# Sheet1.net
KiCad netlist of a schematic drawn in Altium Designer
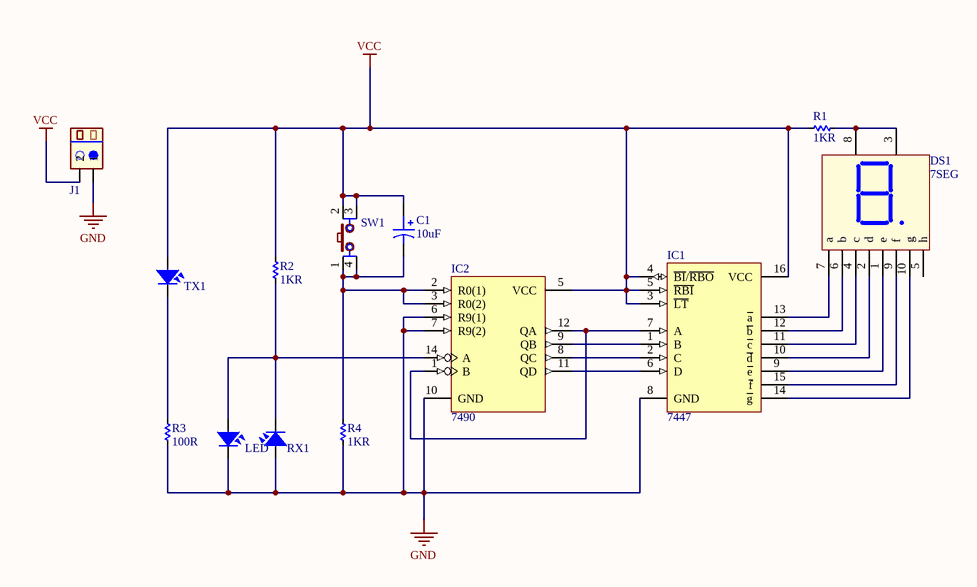
[diagram p0: Sheet1.SchDoc]

(export (version "E")
  (design (tool "Eeschema 10.0.6"))
  (components
    (comp (ref "C1")
      (value "10uF")
      (footprint "RADIAL C")
      (description "Polarized Capacitor")
      (fields (field (name "Comment") "Cap Pol") (field (name "PUBLISHER") "Altium Limited"))
      (libsource (lib "hphonglib") (part "Cap Pol"))
    )
    (comp (ref "DS1")
      (value "7SEG")
      (footprint "LED7SEG-1-0.56")
      (description "14.2 mm General Purpose Blue 7-Segment Display: CC, RH DP, Gray Surface")
      (fields (field (name "PUBLISHER") "Altium Limited"))
      (libsource (lib "LIBRARY") (part "LED7SEG-1"))
    )
    (comp (ref "IC1")
      (value "7447")
      (footprint "DIP16")
      (description "BCD to 7-Segment Decoder/Driver")
      (libsource (lib "LIBRARY") (part "7447"))
    )
    (comp (ref "IC2")
      (value "7490")
      (footprint "DIP14")
      (description "4-Bit Decade Counter")
      (libsource (lib "LIBRARY") (part "7490"))
    )
    (comp (ref "J1")
      (value "CON.Domino2")
      (footprint "Domino 2M")
      (description "2 pins Domino Header")
      (fields (field (name "PUBLISHER") "Hoang Nguyen"))
      (libsource (lib "hphonglib") (part "CON.Domino2"))
    )
    (comp (ref "LED")
      (value "LED")
      (footprint "LED-5-RED")
      (description "LED Single colour Green and Red")
      (libsource (lib "LIBRARY") (part "LED"))
    )
    (comp (ref "R1")
      (value "1KR")
      (footprint "RES-1/4W")
      (description "Res")
      (fields
        (field (name "MANUFACTURER") "Generic Components")
        (field (name "PUBLISHER") "Altium Hobart Technology Centre")
      )
      (libsource (lib "LIBRARY") (part "Res"))
    )
    (comp (ref "R2")
      (value "1KR")
      (footprint "RES-1/4W")
      (description "Res")
      (fields
        (field (name "MANUFACTURER") "Generic Components")
        (field (name "PUBLISHER") "Altium Hobart Technology Centre")
      )
      (libsource (lib "LIBRARY") (part "Res"))
    )
    (comp (ref "R3")
      (value "100R")
      (footprint "RES-1/4W")
      (description "Res")
      (fields
        (field (name "MANUFACTURER") "Generic Components")
        (field (name "PUBLISHER") "Altium Hobart Technology Centre")
      )
      (libsource (lib "LIBRARY") (part "Res"))
    )
    (comp (ref "R4")
      (value "1KR")
      (footprint "RES-1/4W")
      (description "Res")
      (fields
        (field (name "MANUFACTURER") "Generic Components")
        (field (name "PUBLISHER") "Altium Hobart Technology Centre")
      )
      (libsource (lib "LIBRARY") (part "Res"))
    )
    (comp (ref "RX1")
      (value "LED")
      (footprint "LED-5MM-BLUE")
      (description "LED Single colour Green and Red")
      (libsource (lib "LIBRARY") (part "LED"))
    )
    (comp (ref "SW1")
      (value "SW")
      (footprint "SW2-DIP")
      (description "Switch button 4 pin")
      (libsource (lib "LIBRARY") (part "SW4"))
    )
    (comp (ref "TX1")
      (value "LED")
      (footprint "LED-5MM-WHITE")
      (description "LED Single colour Green and Red")
      (libsource (lib "LIBRARY") (part "LED"))
    )
  )
  (nets
    (net (code "1") (name "GND") (class "Default")
      (node (ref "IC1") (pin "8") (pinfunction "GND_8") (pintype "power_in"))
      (node (ref "IC2") (pin "10") (pinfunction "GND_10") (pintype "power_in"))
      (node (ref "IC2") (pin "6") (pinfunction "R9(1)_6") (pintype "input"))
      (node (ref "IC2") (pin "7") (pinfunction "R9(2)_7") (pintype "input"))
      (node (ref "J1") (pin "1") (pinfunction "1_1") (pintype "passive"))
      (node (ref "LED") (pin "2") (pinfunction "2_2") (pintype "passive"))
      (node (ref "R3") (pin "2") (pinfunction "2_2") (pintype "passive"))
      (node (ref "R4") (pin "2") (pinfunction "2_2") (pintype "passive"))
      (node (ref "RX1") (pin "1") (pinfunction "1_1") (pintype "passive"))
    )
    (net (code "2") (name "Net-(DS1-Vcc-Pad3)") (class "Default")
      (node (ref "DS1") (pin "3") (pinfunction "Vcc_3") (pintype "passive"))
      (node (ref "DS1") (pin "8") (pinfunction "Vcc_8") (pintype "passive"))
      (node (ref "R1") (pin "2") (pinfunction "2_2") (pintype "passive"))
    )
    (net (code "3") (name "Net-(DS1-a)") (class "Default")
      (node (ref "DS1") (pin "7") (pinfunction "a_7") (pintype "passive"))
      (node (ref "IC1") (pin "13") (pinfunction "~{a}_13") (pintype "open_collector"))
    )
    (net (code "4") (name "Net-(DS1-b)") (class "Default")
      (node (ref "DS1") (pin "6") (pinfunction "b_6") (pintype "passive"))
      (node (ref "IC1") (pin "12") (pinfunction "~{b}_12") (pintype "open_collector"))
    )
    (net (code "5") (name "Net-(DS1-c)") (class "Default")
      (node (ref "DS1") (pin "4") (pinfunction "c_4") (pintype "passive"))
      (node (ref "IC1") (pin "11") (pinfunction "~{c}_11") (pintype "open_collector"))
    )
    (net (code "6") (name "Net-(DS1-d)") (class "Default")
      (node (ref "DS1") (pin "2") (pinfunction "d_2") (pintype "passive"))
      (node (ref "IC1") (pin "10") (pinfunction "~{d}_10") (pintype "open_collector"))
    )
    (net (code "7") (name "Net-(DS1-e)") (class "Default")
      (node (ref "DS1") (pin "1") (pinfunction "e_1") (pintype "passive"))
      (node (ref "IC1") (pin "9") (pinfunction "~{e}_9") (pintype "open_collector"))
    )
    (net (code "8") (name "Net-(DS1-f)") (class "Default")
      (node (ref "DS1") (pin "9") (pinfunction "f_9") (pintype "passive"))
      (node (ref "IC1") (pin "15") (pinfunction "~{f}_15") (pintype "open_collector"))
    )
    (net (code "9") (name "Net-(DS1-g)") (class "Default")
      (node (ref "DS1") (pin "10") (pinfunction "g_10") (pintype "passive"))
      (node (ref "IC1") (pin "14") (pinfunction "~{g}_14") (pintype "open_collector"))
    )
    (net (code "10") (name "Net-(IC1-A)") (class "Default")
      (node (ref "IC1") (pin "7") (pinfunction "A_7") (pintype "input"))
      (node (ref "IC2") (pin "1") (pinfunction "B_1") (pintype "input"))
      (node (ref "IC2") (pin "12") (pinfunction "QA_12") (pintype "output"))
    )
    (net (code "11") (name "Net-(IC1-B)") (class "Default")
      (node (ref "IC1") (pin "1") (pinfunction "B_1") (pintype "input"))
      (node (ref "IC2") (pin "9") (pinfunction "QB_9") (pintype "output"))
    )
    (net (code "12") (name "Net-(IC1-C)") (class "Default")
      (node (ref "IC1") (pin "2") (pinfunction "C_2") (pintype "input"))
      (node (ref "IC2") (pin "8") (pinfunction "QC_8") (pintype "output"))
    )
    (net (code "13") (name "Net-(IC1-D)") (class "Default")
      (node (ref "IC1") (pin "6") (pinfunction "D_6") (pintype "input"))
      (node (ref "IC2") (pin "11") (pinfunction "QD_11") (pintype "output"))
    )
    (net (code "14") (name "Net-(IC2-A)") (class "Default")
      (node (ref "IC2") (pin "14") (pinfunction "A_14") (pintype "input"))
      (node (ref "LED") (pin "1") (pinfunction "1_1") (pintype "passive"))
      (node (ref "R2") (pin "2") (pinfunction "2_2") (pintype "passive"))
      (node (ref "RX1") (pin "2") (pinfunction "2_2") (pintype "passive"))
    )
    (net (code "15") (name "Net-(IC2-R0(1))") (class "Default")
      (node (ref "C1") (pin "2") (pinfunction "2_2") (pintype "passive"))
      (node (ref "IC2") (pin "2") (pinfunction "R0(1)_2") (pintype "input"))
      (node (ref "IC2") (pin "3") (pinfunction "R0(2)_3") (pintype "input"))
      (node (ref "R4") (pin "1") (pinfunction "1_1") (pintype "passive"))
      (node (ref "SW1") (pin "1") (pintype "passive"))
      (node (ref "SW1") (pin "4") (pinfunction "4_4") (pintype "passive"))
    )
    (net (code "16") (name "Net-(R3-Pad1)") (class "Default")
      (node (ref "R3") (pin "1") (pinfunction "1_1") (pintype "passive"))
      (node (ref "TX1") (pin "2") (pinfunction "2_2") (pintype "passive"))
    )
    (net (code "17") (name "VCC") (class "Default")
      (node (ref "C1") (pin "1") (pinfunction "1_1") (pintype "passive"))
      (node (ref "IC1") (pin "16") (pinfunction "VCC_16") (pintype "power_in"))
      (node (ref "IC1") (pin "3") (pinfunction "~{LT}_3") (pintype "input"))
      (node (ref "IC1") (pin "4") (pinfunction "~{BI}/~{RBO}_4") (pintype "bidirectional"))
      (node (ref "IC1") (pin "5") (pinfunction "~{RBI}_5") (pintype "input"))
      (node (ref "IC2") (pin "5") (pinfunction "VCC_5") (pintype "power_in"))
      (node (ref "J1") (pin "2") (pinfunction "2_2") (pintype "passive"))
      (node (ref "R1") (pin "1") (pinfunction "1_1") (pintype "passive"))
      (node (ref "R2") (pin "1") (pinfunction "1_1") (pintype "passive"))
      (node (ref "SW1") (pin "2") (pinfunction "2_2") (pintype "passive"))
      (node (ref "SW1") (pin "3") (pinfunction "3_3") (pintype "passive"))
      (node (ref "TX1") (pin "1") (pinfunction "1_1") (pintype "passive"))
    )
    (net (code "18") (name "unconnected-(DS1-h-Pad5)") (class "Default")
      (node (ref "DS1") (pin "5") (pinfunction "h_5") (pintype "passive"))
    )
  )
)
